# connections.net
KiCad netlist of a schematic drawn in Altium Designer
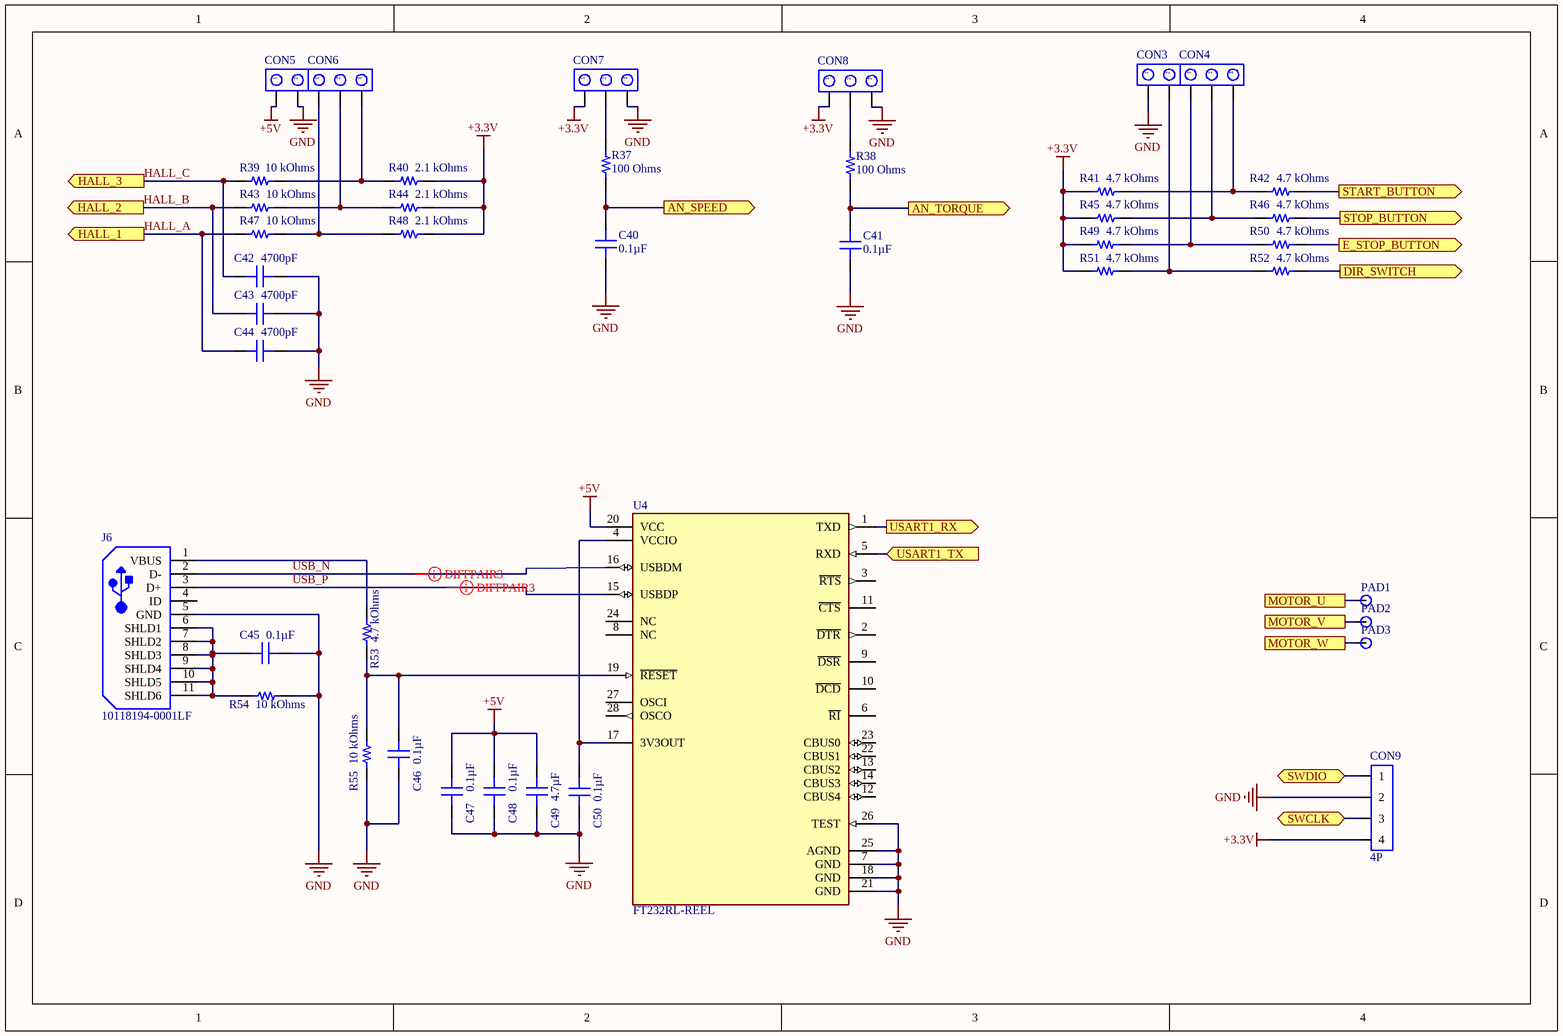
[diagram p0: connections.SchDoc]

(export (version "E")
  (design (tool "Eeschema 10.0.6"))
  (components
    (comp (ref "C40")
      (value "0.1µF")
      (footprint "CAP 0402_1005")
      (description "CAP CER 0.1UF 16V X7R 0402")
      (fields (field (name "PART NUMBER") "C0402C104M4RACTU") (field (name "MANUFACTURER") "KEMET"))
      (libsource (lib "Celestial Altium Library - altium_library") (part "Capacitor"))
    )
    (comp (ref "C41")
      (value "0.1µF")
      (footprint "CAP 0402_1005")
      (description "CAP CER 0.1UF 16V X7R 0402")
      (fields (field (name "PART NUMBER") "C0402C104M4RACTU") (field (name "MANUFACTURER") "KEMET"))
      (libsource (lib "Celestial Altium Library - altium_library") (part "Capacitor"))
    )
    (comp (ref "C42")
      (value "4700pF")
      (footprint "CAP 0603_1608")
      (description "CAP CER 0603 4.7NF 16V X7R 10%")
      (fields (field (name "PART NUMBER") "C0603C472K4RECAUTO") (field (name "MANUFACTURER") "KEMET"))
      (libsource (lib "Celestial Altium Library - altium_library") (part "Capacitor"))
    )
    (comp (ref "C43")
      (value "4700pF")
      (footprint "CAP 0603_1608")
      (description "CAP CER 0603 4.7NF 16V X7R 10%")
      (fields (field (name "PART NUMBER") "C0603C472K4RECAUTO") (field (name "MANUFACTURER") "KEMET"))
      (libsource (lib "Celestial Altium Library - altium_library") (part "Capacitor"))
    )
    (comp (ref "C44")
      (value "4700pF")
      (footprint "CAP 0603_1608")
      (description "CAP CER 0603 4.7NF 16V X7R 10%")
      (fields (field (name "PART NUMBER") "C0603C472K4RECAUTO") (field (name "MANUFACTURER") "KEMET"))
      (libsource (lib "Celestial Altium Library - altium_library") (part "Capacitor"))
    )
    (comp (ref "C45")
      (value "0.1µF")
      (footprint "CAP 0402_1005")
      (description "CAP CER 0.1UF 16V X7R 0402")
      (fields (field (name "PART NUMBER") "C0402C104M4RACTU") (field (name "MANUFACTURER") "KEMET"))
      (libsource (lib "Celestial Altium Library - altium_library") (part "Capacitor"))
    )
    (comp (ref "C46")
      (value "0.1µF")
      (footprint "CAP 0402_1005")
      (description "CAP CER 0.1UF 16V X7R 0402")
      (fields (field (name "PART NUMBER") "C0402C104M4RACTU") (field (name "MANUFACTURER") "KEMET"))
      (libsource (lib "Celestial Altium Library - altium_library") (part "Capacitor"))
    )
    (comp (ref "C47")
      (value "0.1µF")
      (footprint "CAP 0402_1005")
      (description "CAP CER 0.1UF 16V X7R 0402")
      (fields (field (name "PART NUMBER") "C0402C104M4RACTU") (field (name "MANUFACTURER") "KEMET"))
      (libsource (lib "Celestial Altium Library - altium_library") (part "Capacitor"))
    )
    (comp (ref "C48")
      (value "0.1µF")
      (footprint "CAP 0402_1005")
      (description "CAP CER 0.1UF 16V X7R 0402")
      (fields (field (name "PART NUMBER") "C0402C104M4RACTU") (field (name "MANUFACTURER") "KEMET"))
      (libsource (lib "Celestial Altium Library - altium_library") (part "Capacitor"))
    )
    (comp (ref "C49")
      (value "4.7µF")
      (footprint "CAP 1206_3216 - 1.0MM")
      (description "CAP CER 4.7UF 25V X7R 1206")
      (fields
        (field (name "PART NUMBER") "C3216X7R1E475K085AB")
        (field (name "MANUFACTURER") "TDK Corporation")
      )
      (libsource (lib "Celestial Altium Library - altium_library") (part "Capacitor"))
    )
    (comp (ref "C50")
      (value "0.1µF")
      (footprint "CAP 0402_1005")
      (description "CAP CER 0.1UF 16V X7R 0402")
      (fields (field (name "PART NUMBER") "C0402C104M4RACTU") (field (name "MANUFACTURER") "KEMET"))
      (libsource (lib "Celestial Altium Library - altium_library") (part "Capacitor"))
    )
    (comp (ref "CON3")
      (value "DG301-5.0-02P-12-00AH")
      (footprint "DG301-5.0-02P-12-00AH")
      (libsource (lib "My_Library_PCB_Terminal") (part "DG301-5.0-02P-12-00AH"))
    )
    (comp (ref "CON4")
      (value "DG301-5.0-03P-12-00AH")
      (footprint "DG301-5.0-03P-12-00AH")
      (libsource (lib "My_Library_PCB_Terminal") (part "DG301-5.0-03P-12-00AH"))
    )
    (comp (ref "CON5")
      (value "DG301-5.0-02P-12-00AH")
      (footprint "DG301-5.0-02P-12-00AH")
      (libsource (lib "My_Library_PCB_Terminal") (part "DG301-5.0-02P-12-00AH"))
    )
    (comp (ref "CON6")
      (value "DG301-5.0-03P-12-00AH")
      (footprint "DG301-5.0-03P-12-00AH")
      (libsource (lib "My_Library_PCB_Terminal") (part "DG301-5.0-03P-12-00AH"))
    )
    (comp (ref "CON7")
      (value "DG301-5.0-03P-12-00AH")
      (footprint "DG301-5.0-03P-12-00AH")
      (libsource (lib "My_Library_PCB_Terminal") (part "DG301-5.0-03P-12-00AH"))
    )
    (comp (ref "CON8")
      (value "DG301-5.0-03P-12-00AH")
      (footprint "DG301-5.0-03P-12-00AH")
      (libsource (lib "My_Library_PCB_Terminal") (part "DG301-5.0-03P-12-00AH"))
    )
    (comp (ref "CON9")
      (value "4P")
      (footprint "Single_THT_4P_2.54Pitch_6Height_180C")
      (libsource (lib "My_Library_Header") (part "Single 4P 2.54mm"))
    )
    (comp (ref "J6")
      (value "10118194-0001LF")
      (footprint "FCI-10118194-0001LF-5_V")
      (description "Micro USB B Type Receptacle, 1.8 A, -55 to 85 degC, 5-Pin SMD, RoHS, Tape and Reel")
      (fields (field (name "MANUFACTURER") "Amphenol FCI"))
      (libsource (lib "MY_Library_USB_Connectors") (part "KLS1-238"))
    )
    (comp (ref "PAD1")
      (value "Single Pad 4mm")
      (footprint "PCBComponent_1")
      (libsource (lib "My_Library_Single_Pad") (part "Single Pad 4mm"))
    )
    (comp (ref "PAD2")
      (value "Single Pad 4mm")
      (footprint "PCBComponent_1")
      (libsource (lib "My_Library_Single_Pad") (part "Single Pad 4mm"))
    )
    (comp (ref "PAD3")
      (value "Single Pad 4mm")
      (footprint "PCBComponent_1")
      (libsource (lib "My_Library_Single_Pad") (part "Single Pad 4mm"))
    )
    (comp (ref "R37")
      (value "100 Ohms")
      (footprint "RES 1206_3216")
      (description "RES SMD 100 OHM 1% 1/4W 1206")
      (fields
        (field (name "PART NUMBER") "CRG1206F100R")
        (field (name "MANUFACTURER") "TE Connectivity Passive Product")
      )
      (libsource (lib "Celestial Altium Library - altium_library") (part "Resistor"))
    )
    (comp (ref "R38")
      (value "100 Ohms")
      (footprint "RES 1206_3216")
      (description "RES SMD 100 OHM 1% 1/4W 1206")
      (fields
        (field (name "PART NUMBER") "CRG1206F100R")
        (field (name "MANUFACTURER") "TE Connectivity Passive Product")
      )
      (libsource (lib "Celestial Altium Library - altium_library") (part "Resistor"))
    )
    (comp (ref "R39")
      (value "10 kOhms")
      (footprint "RES 1206_3216")
      (description "RES SMD 10K OHM 1% 1/4W 1206")
      (fields
        (field (name "PART NUMBER") "CRG1206F10K")
        (field (name "MANUFACTURER") "TE Connectivity Passive Product")
      )
      (libsource (lib "Celestial Altium Library - altium_library") (part "Resistor"))
    )
    (comp (ref "R40")
      (value "2.1 kOhms")
      (footprint "RES 1206_3216")
      (description "RES SMD 2.1K OHM 1% 1/4W 1206")
      (fields (field (name "PART NUMBER") "RC1206FR-072K1L") (field (name "MANUFACTURER") "Yageo"))
      (libsource (lib "Celestial Altium Library - altium_library") (part "Resistor"))
    )
    (comp (ref "R41")
      (value "4.7 kOhms")
      (footprint "RES 1206_3216")
      (description "RES SMD 4.7K OHM 1% 1/4W 1206")
      (fields
        (field (name "PART NUMBER") "CRG1206F4K7")
        (field (name "MANUFACTURER") "TE Connectivity Passive Product")
      )
      (libsource (lib "Celestial Altium Library - altium_library") (part "Resistor"))
    )
    (comp (ref "R42")
      (value "4.7 kOhms")
      (footprint "RES 1206_3216")
      (description "RES SMD 4.7K OHM 1% 1/4W 1206")
      (fields
        (field (name "PART NUMBER") "CRG1206F4K7")
        (field (name "MANUFACTURER") "TE Connectivity Passive Product")
      )
      (libsource (lib "Celestial Altium Library - altium_library") (part "Resistor"))
    )
    (comp (ref "R43")
      (value "10 kOhms")
      (footprint "RES 1206_3216")
      (description "RES SMD 10K OHM 1% 1/4W 1206")
      (fields
        (field (name "PART NUMBER") "CRG1206F10K")
        (field (name "MANUFACTURER") "TE Connectivity Passive Product")
      )
      (libsource (lib "Celestial Altium Library - altium_library") (part "Resistor"))
    )
    (comp (ref "R44")
      (value "2.1 kOhms")
      (footprint "RES 1206_3216")
      (description "RES SMD 2.1K OHM 1% 1/4W 1206")
      (fields (field (name "PART NUMBER") "RC1206FR-072K1L") (field (name "MANUFACTURER") "Yageo"))
      (libsource (lib "Celestial Altium Library - altium_library") (part "Resistor"))
    )
    (comp (ref "R45")
      (value "4.7 kOhms")
      (footprint "RES 1206_3216")
      (description "RES SMD 4.7K OHM 1% 1/4W 1206")
      (fields
        (field (name "PART NUMBER") "CRG1206F4K7")
        (field (name "MANUFACTURER") "TE Connectivity Passive Product")
      )
      (libsource (lib "Celestial Altium Library - altium_library") (part "Resistor"))
    )
    (comp (ref "R46")
      (value "4.7 kOhms")
      (footprint "RES 1206_3216")
      (description "RES SMD 4.7K OHM 1% 1/4W 1206")
      (fields
        (field (name "PART NUMBER") "CRG1206F4K7")
        (field (name "MANUFACTURER") "TE Connectivity Passive Product")
      )
      (libsource (lib "Celestial Altium Library - altium_library") (part "Resistor"))
    )
    (comp (ref "R47")
      (value "10 kOhms")
      (footprint "RES 1206_3216")
      (description "RES SMD 10K OHM 1% 1/4W 1206")
      (fields
        (field (name "PART NUMBER") "CRG1206F10K")
        (field (name "MANUFACTURER") "TE Connectivity Passive Product")
      )
      (libsource (lib "Celestial Altium Library - altium_library") (part "Resistor"))
    )
    (comp (ref "R48")
      (value "2.1 kOhms")
      (footprint "RES 1206_3216")
      (description "RES SMD 2.1K OHM 1% 1/4W 1206")
      (fields (field (name "PART NUMBER") "RC1206FR-072K1L") (field (name "MANUFACTURER") "Yageo"))
      (libsource (lib "Celestial Altium Library - altium_library") (part "Resistor"))
    )
    (comp (ref "R49")
      (value "4.7 kOhms")
      (footprint "RES 1206_3216")
      (description "RES SMD 4.7K OHM 1% 1/4W 1206")
      (fields
        (field (name "PART NUMBER") "CRG1206F4K7")
        (field (name "MANUFACTURER") "TE Connectivity Passive Product")
      )
      (libsource (lib "Celestial Altium Library - altium_library") (part "Resistor"))
    )
    (comp (ref "R50")
      (value "4.7 kOhms")
      (footprint "RES 1206_3216")
      (description "RES SMD 4.7K OHM 1% 1/4W 1206")
      (fields
        (field (name "PART NUMBER") "CRG1206F4K7")
        (field (name "MANUFACTURER") "TE Connectivity Passive Product")
      )
      (libsource (lib "Celestial Altium Library - altium_library") (part "Resistor"))
    )
    (comp (ref "R51")
      (value "4.7 kOhms")
      (footprint "RES 1206_3216")
      (description "RES SMD 4.7K OHM 1% 1/4W 1206")
      (fields
        (field (name "PART NUMBER") "CRG1206F4K7")
        (field (name "MANUFACTURER") "TE Connectivity Passive Product")
      )
      (libsource (lib "Celestial Altium Library - altium_library") (part "Resistor"))
    )
    (comp (ref "R52")
      (value "4.7 kOhms")
      (footprint "RES 1206_3216")
      (description "RES SMD 4.7K OHM 1% 1/4W 1206")
      (fields
        (field (name "PART NUMBER") "CRG1206F4K7")
        (field (name "MANUFACTURER") "TE Connectivity Passive Product")
      )
      (libsource (lib "Celestial Altium Library - altium_library") (part "Resistor"))
    )
    (comp (ref "R53")
      (value "4.7 kOhms")
      (footprint "RES 1206_3216")
      (description "RES SMD 4.7K OHM 1% 1/4W 1206")
      (fields
        (field (name "PART NUMBER") "CRG1206F4K7")
        (field (name "MANUFACTURER") "TE Connectivity Passive Product")
      )
      (libsource (lib "Celestial Altium Library - altium_library") (part "Resistor"))
    )
    (comp (ref "R54")
      (value "10 kOhms")
      (footprint "RES 1206_3216")
      (description "RES SMD 10K OHM 1% 1/4W 1206")
      (fields
        (field (name "PART NUMBER") "CRG1206F10K")
        (field (name "MANUFACTURER") "TE Connectivity Passive Product")
      )
      (libsource (lib "Celestial Altium Library - altium_library") (part "Resistor"))
    )
    (comp (ref "R55")
      (value "10 kOhms")
      (footprint "RES 1206_3216")
      (description "RES SMD 10K OHM 1% 1/4W 1206")
      (fields
        (field (name "PART NUMBER") "CRG1206F10K")
        (field (name "MANUFACTURER") "TE Connectivity Passive Product")
      )
      (libsource (lib "Celestial Altium Library - altium_library") (part "Resistor"))
    )
    (comp (ref "U4")
      (value "FT232RL-REEL")
      (footprint "FP-SSOP-28-IPC_B")
      (description "IC USB FS SERIAL UART 28-SSOP")
      (fields (field (name "VOLTAGE") "5V"))
      (libsource (lib "My_Library_Interface_IC") (part "FT232R"))
    )
  )
  (nets
    (net (code "1") (name "+3.3V") (class "Default")
      (node (ref "CON7") (pin "1") (pinfunction "1_1") (pintype "passive"))
      (node (ref "CON8") (pin "1") (pinfunction "1_1") (pintype "passive"))
      (node (ref "CON9") (pin "4") (pinfunction "4_4") (pintype "passive"))
      (node (ref "R40") (pin "1") (pinfunction "1_1") (pintype "passive"))
      (node (ref "R41") (pin "1") (pinfunction "1_1") (pintype "passive"))
      (node (ref "R44") (pin "1") (pinfunction "1_1") (pintype "passive"))
      (node (ref "R45") (pin "1") (pinfunction "1_1") (pintype "passive"))
      (node (ref "R48") (pin "1") (pinfunction "1_1") (pintype "passive"))
      (node (ref "R49") (pin "1") (pinfunction "1_1") (pintype "passive"))
      (node (ref "R51") (pin "1") (pinfunction "1_1") (pintype "passive"))
    )
    (net (code "2") (name "+5V") (class "Default")
      (node (ref "C47") (pin "2") (pinfunction "2_2") (pintype "passive"))
      (node (ref "C48") (pin "2") (pinfunction "2_2") (pintype "passive"))
      (node (ref "C49") (pin "2") (pinfunction "2_2") (pintype "passive"))
      (node (ref "CON5") (pin "1") (pinfunction "1_1") (pintype "passive"))
      (node (ref "U4") (pin "20") (pinfunction "VCC_20") (pintype "power_in"))
    )
    (net (code "3") (name "/AN_SPEED") (class "Default")
      (node (ref "C40") (pin "2") (pinfunction "2_2") (pintype "passive"))
      (node (ref "R37") (pin "1") (pinfunction "1_1") (pintype "passive"))
    )
    (net (code "4") (name "/AN_TORQUE") (class "Default")
      (node (ref "C41") (pin "2") (pinfunction "2_2") (pintype "passive"))
      (node (ref "R38") (pin "1") (pinfunction "1_1") (pintype "passive"))
    )
    (net (code "5") (name "/DIR_SWITCH") (class "Default")
      (node (ref "R52") (pin "2") (pinfunction "2_2") (pintype "passive"))
    )
    (net (code "6") (name "/E_STOP_BUTTON") (class "Default")
      (node (ref "R50") (pin "2") (pinfunction "2_2") (pintype "passive"))
    )
    (net (code "7") (name "/HALL_A") (class "Default")
      (node (ref "C44") (pin "2") (pinfunction "2_2") (pintype "passive"))
      (node (ref "R47") (pin "2") (pinfunction "2_2") (pintype "passive"))
    )
    (net (code "8") (name "/HALL_B") (class "Default")
      (node (ref "C43") (pin "2") (pinfunction "2_2") (pintype "passive"))
      (node (ref "R43") (pin "2") (pinfunction "2_2") (pintype "passive"))
    )
    (net (code "9") (name "/HALL_C") (class "Default")
      (node (ref "C42") (pin "2") (pinfunction "2_2") (pintype "passive"))
      (node (ref "R39") (pin "2") (pinfunction "2_2") (pintype "passive"))
    )
    (net (code "10") (name "/MOTOR_U") (class "Default")
      (node (ref "PAD1") (pin "1") (pinfunction "1_1") (pintype "passive"))
    )
    (net (code "11") (name "/MOTOR_V") (class "Default")
      (node (ref "PAD2") (pin "1") (pinfunction "1_1") (pintype "passive"))
    )
    (net (code "12") (name "/MOTOR_W") (class "Default")
      (node (ref "PAD3") (pin "1") (pinfunction "1_1") (pintype "passive"))
    )
    (net (code "13") (name "/START_BUTTON") (class "Default")
      (node (ref "R42") (pin "2") (pinfunction "2_2") (pintype "passive"))
    )
    (net (code "14") (name "/STOP_BUTTON") (class "Default")
      (node (ref "R46") (pin "2") (pinfunction "2_2") (pintype "passive"))
    )
    (net (code "15") (name "/SWCLK") (class "Default")
      (node (ref "CON9") (pin "3") (pinfunction "3_3") (pintype "passive"))
    )
    (net (code "16") (name "/SWDIO") (class "Default")
      (node (ref "CON9") (pin "1") (pinfunction "1_1") (pintype "passive"))
    )
    (net (code "17") (name "/USART1_RX") (class "Default")
      (node (ref "U4") (pin "1") (pinfunction "TXD_1") (pintype "output"))
    )
    (net (code "18") (name "/USART1_TX") (class "Default")
      (node (ref "U4") (pin "5") (pinfunction "RXD_5") (pintype "input"))
    )
    (net (code "19") (name "/USB_N") (class "Default")
      (node (ref "J6") (pin "2") (pinfunction "D-_2") (pintype "passive"))
      (node (ref "U4") (pin "16") (pinfunction "USBDM_16") (pintype "bidirectional"))
    )
    (net (code "20") (name "/USB_P") (class "Default")
      (node (ref "J6") (pin "3") (pinfunction "D+_3") (pintype "passive"))
      (node (ref "U4") (pin "15") (pinfunction "USBDP_15") (pintype "bidirectional"))
    )
    (net (code "21") (name "GND") (class "Default")
      (node (ref "C40") (pin "1") (pinfunction "1_1") (pintype "passive"))
      (node (ref "C41") (pin "1") (pinfunction "1_1") (pintype "passive"))
      (node (ref "C42") (pin "1") (pinfunction "1_1") (pintype "passive"))
      (node (ref "C43") (pin "1") (pinfunction "1_1") (pintype "passive"))
      (node (ref "C44") (pin "1") (pinfunction "1_1") (pintype "passive"))
      (node (ref "C45") (pin "1") (pinfunction "1_1") (pintype "passive"))
      (node (ref "C46") (pin "1") (pinfunction "1_1") (pintype "passive"))
      (node (ref "C47") (pin "1") (pinfunction "1_1") (pintype "passive"))
      (node (ref "C48") (pin "1") (pinfunction "1_1") (pintype "passive"))
      (node (ref "C49") (pin "1") (pinfunction "1_1") (pintype "passive"))
      (node (ref "C50") (pin "1") (pinfunction "1_1") (pintype "passive"))
      (node (ref "CON3") (pin "1") (pinfunction "1_1") (pintype "passive"))
      (node (ref "CON5") (pin "2") (pinfunction "2_2") (pintype "passive"))
      (node (ref "CON7") (pin "3") (pinfunction "3_3") (pintype "passive"))
      (node (ref "CON8") (pin "3") (pinfunction "3_3") (pintype "passive"))
      (node (ref "CON9") (pin "2") (pinfunction "2_2") (pintype "passive"))
      (node (ref "J6") (pin "5") (pinfunction "GND_5") (pintype "passive"))
      (node (ref "R54") (pin "1") (pinfunction "1_1") (pintype "passive"))
      (node (ref "R55") (pin "1") (pinfunction "1_1") (pintype "passive"))
      (node (ref "U4") (pin "18") (pinfunction "GND_18") (pintype "power_in"))
      (node (ref "U4") (pin "21") (pinfunction "GND_21") (pintype "power_in"))
      (node (ref "U4") (pin "25") (pinfunction "AGND_25") (pintype "power_in"))
      (node (ref "U4") (pin "26") (pinfunction "TEST_26") (pintype "input"))
      (node (ref "U4") (pin "7") (pinfunction "GND_7") (pintype "power_in"))
    )
    (net (code "22") (name "Net-(CON3-Pad2)") (class "Default")
      (node (ref "CON3") (pin "2") (pinfunction "2_2") (pintype "passive"))
      (node (ref "R51") (pin "2") (pinfunction "2_2") (pintype "passive"))
      (node (ref "R52") (pin "1") (pinfunction "1_1") (pintype "passive"))
    )
    (net (code "23") (name "Net-(CON4-Pad1)") (class "Default")
      (node (ref "CON4") (pin "1") (pinfunction "1_1") (pintype "passive"))
      (node (ref "R49") (pin "2") (pinfunction "2_2") (pintype "passive"))
      (node (ref "R50") (pin "1") (pinfunction "1_1") (pintype "passive"))
    )
    (net (code "24") (name "Net-(CON4-Pad2)") (class "Default")
      (node (ref "CON4") (pin "2") (pinfunction "2_2") (pintype "passive"))
      (node (ref "R45") (pin "2") (pinfunction "2_2") (pintype "passive"))
      (node (ref "R46") (pin "1") (pinfunction "1_1") (pintype "passive"))
    )
    (net (code "25") (name "Net-(CON4-Pad3)") (class "Default")
      (node (ref "CON4") (pin "3") (pinfunction "3_3") (pintype "passive"))
      (node (ref "R41") (pin "2") (pinfunction "2_2") (pintype "passive"))
      (node (ref "R42") (pin "1") (pinfunction "1_1") (pintype "passive"))
    )
    (net (code "26") (name "Net-(CON6-Pad1)") (class "Default")
      (node (ref "CON6") (pin "1") (pinfunction "1_1") (pintype "passive"))
      (node (ref "R47") (pin "1") (pinfunction "1_1") (pintype "passive"))
      (node (ref "R48") (pin "2") (pinfunction "2_2") (pintype "passive"))
    )
    (net (code "27") (name "Net-(CON6-Pad2)") (class "Default")
      (node (ref "CON6") (pin "2") (pinfunction "2_2") (pintype "passive"))
      (node (ref "R43") (pin "1") (pinfunction "1_1") (pintype "passive"))
      (node (ref "R44") (pin "2") (pinfunction "2_2") (pintype "passive"))
    )
    (net (code "28") (name "Net-(CON6-Pad3)") (class "Default")
      (node (ref "CON6") (pin "3") (pinfunction "3_3") (pintype "passive"))
      (node (ref "R39") (pin "1") (pinfunction "1_1") (pintype "passive"))
      (node (ref "R40") (pin "2") (pinfunction "2_2") (pintype "passive"))
    )
    (net (code "29") (name "Net-(CON7-Pad2)") (class "Default")
      (node (ref "CON7") (pin "2") (pinfunction "2_2") (pintype "passive"))
      (node (ref "R37") (pin "2") (pinfunction "2_2") (pintype "passive"))
    )
    (net (code "30") (name "Net-(CON8-Pad2)") (class "Default")
      (node (ref "CON8") (pin "2") (pinfunction "2_2") (pintype "passive"))
      (node (ref "R38") (pin "2") (pinfunction "2_2") (pintype "passive"))
    )
    (net (code "31") (name "Net-(J6-SHLD1)") (class "Default")
      (node (ref "C45") (pin "2") (pinfunction "2_2") (pintype "passive"))
      (node (ref "J6") (pin "10") (pinfunction "SHLD5_10") (pintype "passive"))
      (node (ref "J6") (pin "11") (pinfunction "SHLD6_11") (pintype "passive"))
      (node (ref "J6") (pin "6") (pinfunction "SHLD1_6") (pintype "passive"))
      (node (ref "J6") (pin "7") (pinfunction "SHLD2_7") (pintype "passive"))
      (node (ref "J6") (pin "8") (pinfunction "SHLD3_8") (pintype "passive"))
      (node (ref "J6") (pin "9") (pinfunction "SHLD4_9") (pintype "passive"))
      (node (ref "R54") (pin "2") (pinfunction "2_2") (pintype "passive"))
    )
    (net (code "32") (name "Net-(J6-VBUS)") (class "Default")
      (node (ref "J6") (pin "1") (pinfunction "VBUS_1") (pintype "passive"))
      (node (ref "R53") (pin "2") (pinfunction "2_2") (pintype "passive"))
    )
    (net (code "33") (name "Net-(U4-3V3OUT)") (class "Default")
      (node (ref "C50") (pin "2") (pinfunction "2_2") (pintype "passive"))
      (node (ref "U4") (pin "17") (pinfunction "3V3OUT_17") (pintype "power_in"))
      (node (ref "U4") (pin "4") (pinfunction "VCCIO_4") (pintype "power_in"))
    )
    (net (code "34") (name "Net-(U4-~{RESET})") (class "Default")
      (node (ref "C46") (pin "2") (pinfunction "2_2") (pintype "passive"))
      (node (ref "R53") (pin "1") (pinfunction "1_1") (pintype "passive"))
      (node (ref "R55") (pin "2") (pinfunction "2_2") (pintype "passive"))
      (node (ref "U4") (pin "19") (pinfunction "~{RESET}_19") (pintype "input"))
    )
    (net (code "35") (name "unconnected-(J6-ID-Pad4)") (class "Default")
      (node (ref "J6") (pin "4") (pinfunction "ID_4") (pintype "passive"))
    )
    (net (code "36") (name "unconnected-(U4-CBUS0-Pad23)") (class "Default")
      (node (ref "U4") (pin "23") (pinfunction "CBUS0_23") (pintype "bidirectional"))
    )
    (net (code "37") (name "unconnected-(U4-CBUS1-Pad22)") (class "Default")
      (node (ref "U4") (pin "22") (pinfunction "CBUS1_22") (pintype "bidirectional"))
    )
    (net (code "38") (name "unconnected-(U4-CBUS2-Pad13)") (class "Default")
      (node (ref "U4") (pin "13") (pinfunction "CBUS2_13") (pintype "bidirectional"))
    )
    (net (code "39") (name "unconnected-(U4-CBUS3-Pad14)") (class "Default")
      (node (ref "U4") (pin "14") (pinfunction "CBUS3_14") (pintype "bidirectional"))
    )
    (net (code "40") (name "unconnected-(U4-CBUS4-Pad12)") (class "Default")
      (node (ref "U4") (pin "12") (pinfunction "CBUS4_12") (pintype "bidirectional"))
    )
    (net (code "41") (name "unconnected-(U4-NC-Pad8)") (class "Default")
      (node (ref "U4") (pin "8") (pinfunction "NC_8") (pintype "passive"))
    )
    (net (code "42") (name "unconnected-(U4-NC-Pad24)") (class "Default")
      (node (ref "U4") (pin "24") (pinfunction "NC_24") (pintype "passive"))
    )
    (net (code "43") (name "unconnected-(U4-OSCI-Pad27)") (class "Default")
      (node (ref "U4") (pin "27") (pinfunction "OSCI_27") (pintype "passive"))
    )
    (net (code "44") (name "unconnected-(U4-OSCO-Pad28)") (class "Default")
      (node (ref "U4") (pin "28") (pinfunction "OSCO_28") (pintype "output"))
    )
    (net (code "45") (name "unconnected-(U4-~{CTS}-Pad11)") (class "Default")
      (node (ref "U4") (pin "11") (pinfunction "~{CTS}_11") (pintype "passive"))
    )
    (net (code "46") (name "unconnected-(U4-~{DCD}-Pad10)") (class "Default")
      (node (ref "U4") (pin "10") (pinfunction "~{DCD}_10") (pintype "passive"))
    )
    (net (code "47") (name "unconnected-(U4-~{DSR}-Pad9)") (class "Default")
      (node (ref "U4") (pin "9") (pinfunction "~{DSR}_9") (pintype "passive"))
    )
    (net (code "48") (name "unconnected-(U4-~{DTR}-Pad2)") (class "Default")
      (node (ref "U4") (pin "2") (pinfunction "~{DTR}_2") (pintype "output"))
    )
    (net (code "49") (name "unconnected-(U4-~{RI}-Pad6)") (class "Default")
      (node (ref "U4") (pin "6") (pinfunction "~{RI}_6") (pintype "passive"))
    )
    (net (code "50") (name "unconnected-(U4-~{RTS}-Pad3)") (class "Default")
      (node (ref "U4") (pin "3") (pinfunction "~{RTS}_3") (pintype "output"))
    )
  )
)
